# VR_joypad.net
KiCad netlist of a schematic drawn in Altium Designer
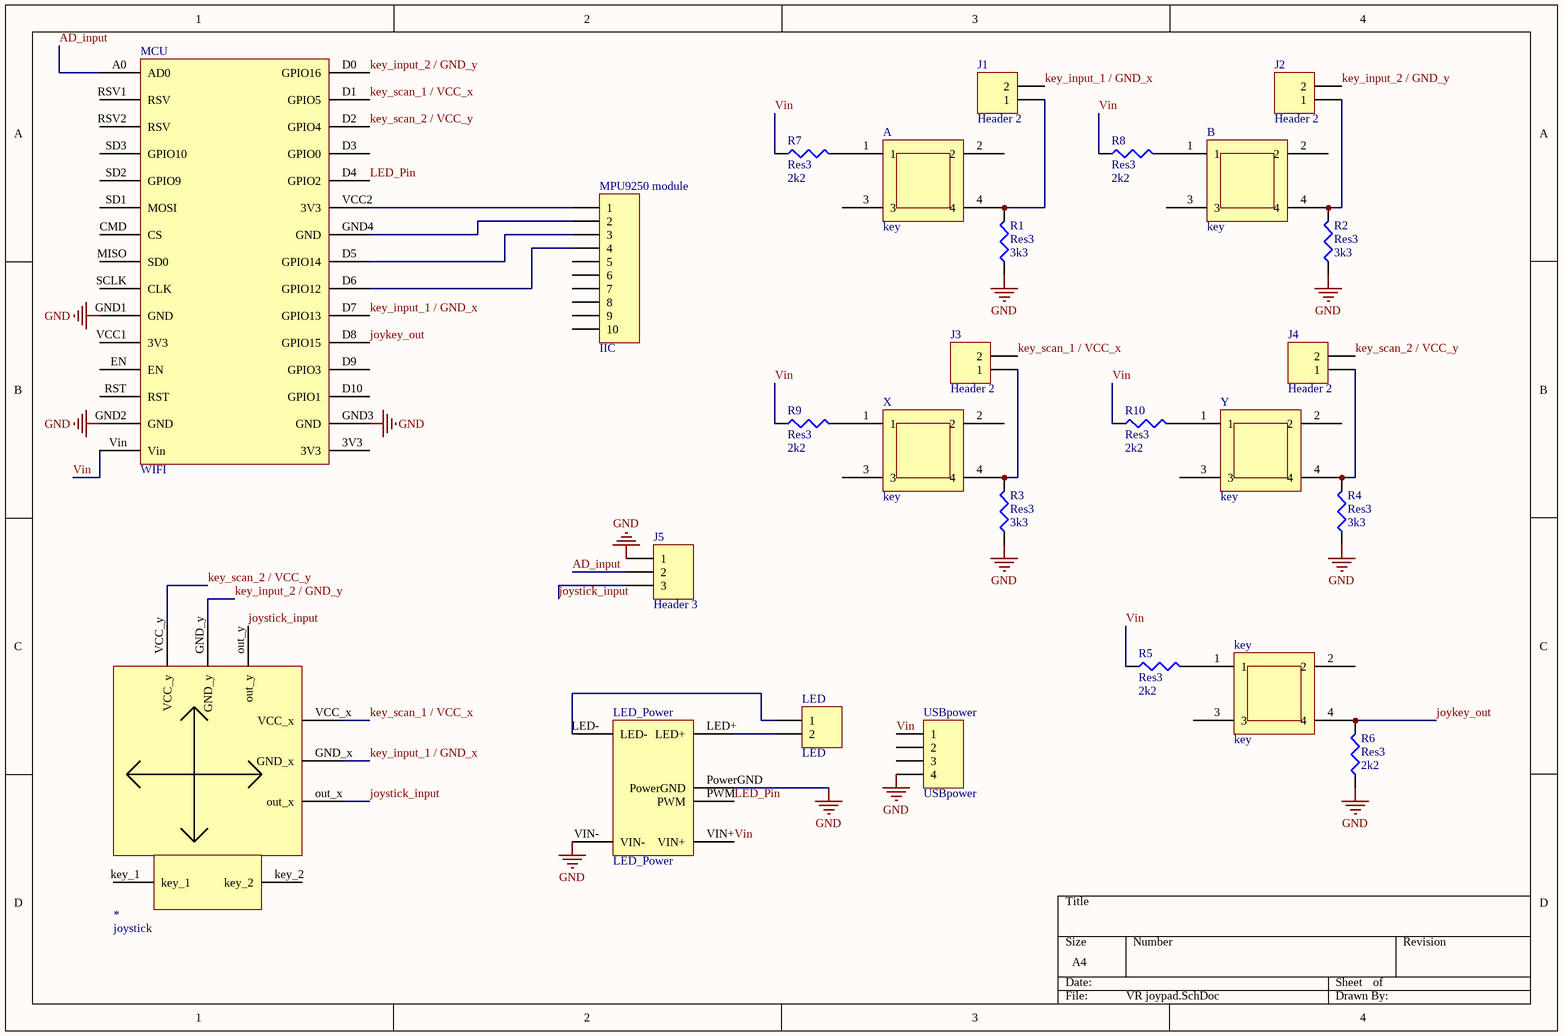
[diagram p0: VR joypad.SchDoc]

(export (version "E")
  (design (tool "Eeschema 10.0.6"))
  (components
    (comp (ref "*") (value "joystick") (footprint "joystick") (libsource (lib "VR joypad") (part "joystick")))
    (comp (ref "A")
      (value "key")
      (footprint "PCBComponent_1 - duplicate")
      (libsource (lib "VR joypad") (part "key"))
    )
    (comp (ref "B")
      (value "key")
      (footprint "PCBComponent_1 - duplicate")
      (libsource (lib "VR joypad") (part "key"))
    )
    (comp (ref "J1")
      (value "Header 2")
      (footprint "HDR1X2")
      (description "Header, 2-Pin")
      (fields (field (name "PUBLISHER") "Altium Limited"))
      (libsource (lib "") (part "Header 2_1"))
    )
    (comp (ref "J2")
      (value "Header 2")
      (footprint "HDR1X2")
      (description "Header, 2-Pin")
      (fields (field (name "PUBLISHER") "Altium Limited"))
      (libsource (lib "") (part "Header 2_1"))
    )
    (comp (ref "J3")
      (value "Header 2")
      (footprint "HDR1X2")
      (description "Header, 2-Pin")
      (fields (field (name "PUBLISHER") "Altium Limited"))
      (libsource (lib "") (part "Header 2_1"))
    )
    (comp (ref "J4")
      (value "Header 2")
      (footprint "HDR1X2")
      (description "Header, 2-Pin")
      (fields (field (name "PUBLISHER") "Altium Limited"))
      (libsource (lib "") (part "Header 2_1"))
    )
    (comp (ref "J5")
      (value "Header 3")
      (footprint "HDR1X3")
      (description "Header, 3-Pin")
      (fields (field (name "PUBLISHER") "Altium Limited"))
      (libsource (lib "Miscellaneous Connectors") (part "Header 3"))
    )
    (comp (ref "key")
      (value "key")
      (footprint "PCBComponent_1 - duplicate")
      (libsource (lib "VR joypad") (part "key"))
    )
    (comp (ref "LED")
      (value "LED")
      (footprint "HDR1X2")
      (description "Header, 2-Pin")
      (fields (field (name "PUBLISHER") "Altium Limited"))
      (libsource (lib "Miscellaneous Connectors") (part "Header 2"))
    )
    (comp (ref "LED_Power")
      (value "LED_Power")
      (footprint "PCBComponent_1 - duplicate1")
      (libsource (lib "VR joypad") (part "Power"))
    )
    (comp (ref "MCU")
      (value "WIFI")
      (footprint "PCBComponent_1")
      (libsource (lib "VR joypad") (part "Component_1"))
    )
    (comp (ref "MPU9250 module")
      (value "IIC")
      (footprint "HDR1X10")
      (description "Header, 10-Pin")
      (fields (field (name "PUBLISHER") "Altium Limited"))
      (libsource (lib "Miscellaneous Connectors") (part "Header 10"))
    )
    (comp (ref "R1")
      (value "Res3")
      (footprint "6-0805_N")
      (description "Resistor")
      (fields (field (name "ALTIUM_VALUE") "3k3") (field (name "PUBLISHER") "Altium Limited"))
      (libsource (lib "Miscellaneous Devices") (part "Res3"))
    )
    (comp (ref "R2")
      (value "Res3")
      (footprint "6-0805_N")
      (description "Resistor")
      (fields (field (name "ALTIUM_VALUE") "3k3") (field (name "PUBLISHER") "Altium Limited"))
      (libsource (lib "Miscellaneous Devices") (part "Res3"))
    )
    (comp (ref "R3")
      (value "Res3")
      (footprint "6-0805_N")
      (description "Resistor")
      (fields (field (name "ALTIUM_VALUE") "3k3") (field (name "PUBLISHER") "Altium Limited"))
      (libsource (lib "Miscellaneous Devices") (part "Res3"))
    )
    (comp (ref "R4")
      (value "Res3")
      (footprint "6-0805_N")
      (description "Resistor")
      (fields (field (name "ALTIUM_VALUE") "3k3") (field (name "PUBLISHER") "Altium Limited"))
      (libsource (lib "Miscellaneous Devices") (part "Res3"))
    )
    (comp (ref "R5")
      (value "Res3")
      (footprint "6-0805_N")
      (description "Resistor")
      (fields (field (name "ALTIUM_VALUE") "2k2") (field (name "PUBLISHER") "Altium Limited"))
      (libsource (lib "Miscellaneous Devices") (part "Res3"))
    )
    (comp (ref "R6")
      (value "Res3")
      (footprint "6-0805_N")
      (description "Resistor")
      (fields (field (name "ALTIUM_VALUE") "2k2") (field (name "PUBLISHER") "Altium Limited"))
      (libsource (lib "Miscellaneous Devices") (part "Res3"))
    )
    (comp (ref "R7")
      (value "Res3")
      (footprint "6-0805_N")
      (description "Resistor")
      (fields (field (name "ALTIUM_VALUE") "2k2") (field (name "PUBLISHER") "Altium Limited"))
      (libsource (lib "Miscellaneous Devices") (part "Res3"))
    )
    (comp (ref "R8")
      (value "Res3")
      (footprint "6-0805_N")
      (description "Resistor")
      (fields (field (name "ALTIUM_VALUE") "2k2") (field (name "PUBLISHER") "Altium Limited"))
      (libsource (lib "Miscellaneous Devices") (part "Res3"))
    )
    (comp (ref "R9")
      (value "Res3")
      (footprint "6-0805_N")
      (description "Resistor")
      (fields (field (name "ALTIUM_VALUE") "2k2") (field (name "PUBLISHER") "Altium Limited"))
      (libsource (lib "Miscellaneous Devices") (part "Res3"))
    )
    (comp (ref "R10")
      (value "Res3")
      (footprint "6-0805_N")
      (description "Resistor")
      (fields (field (name "ALTIUM_VALUE") "2k2") (field (name "PUBLISHER") "Altium Limited"))
      (libsource (lib "Miscellaneous Devices") (part "Res3"))
    )
    (comp (ref "USBpower")
      (value "USBpower")
      (footprint "HDR1X4")
      (description "Header, 4-Pin")
      (fields (field (name "PUBLISHER") "Altium Limited"))
      (libsource (lib "Miscellaneous Connectors") (part "Header 4"))
    )
    (comp (ref "X")
      (value "key")
      (footprint "PCBComponent_1 - duplicate")
      (libsource (lib "VR joypad") (part "key"))
    )
    (comp (ref "Y")
      (value "key")
      (footprint "PCBComponent_1 - duplicate")
      (libsource (lib "VR joypad") (part "key"))
    )
  )
  (nets
    (net (code "1") (name "/AD_input") (class "Default")
      (node (ref "J5") (pin "2") (pinfunction "2_2") (pintype "passive"))
      (node (ref "MCU") (pin "A0") (pinfunction "AD0_A0") (pintype "passive"))
    )
    (net (code "2") (name "/LED_Pin") (class "Default")
      (node (ref "LED_Power") (pin "PWM") (pinfunction "PWM_PWM") (pintype "passive"))
      (node (ref "MCU") (pin "D4") (pinfunction "GPIO2_D4") (pintype "passive"))
    )
    (net (code "3") (name "/Vin") (class "Default")
      (node (ref "LED_Power") (pin "VIN+") (pinfunction "VIN+_VIN+") (pintype "passive"))
      (node (ref "MCU") (pin "Vin") (pinfunction "Vin_Vin") (pintype "passive"))
      (node (ref "R10") (pin "1") (pinfunction "1_1") (pintype "passive"))
      (node (ref "R5") (pin "1") (pinfunction "1_1") (pintype "passive"))
      (node (ref "R7") (pin "1") (pinfunction "1_1") (pintype "passive"))
      (node (ref "R8") (pin "1") (pinfunction "1_1") (pintype "passive"))
      (node (ref "R9") (pin "1") (pinfunction "1_1") (pintype "passive"))
      (node (ref "USBpower") (pin "1") (pinfunction "1_1") (pintype "passive"))
    )
    (net (code "4") (name "/joykey_out") (class "Default")
      (node (ref "MCU") (pin "D8") (pinfunction "GPIO15_D8") (pintype "passive"))
      (node (ref "R6") (pin "2") (pinfunction "2_2") (pintype "passive"))
      (node (ref "key") (pin "4") (pinfunction "4_4") (pintype "passive"))
    )
    (net (code "5") (name "/joystick_input") (class "Default")
      (node (ref "*") (pin "out_x") (pinfunction "out_x_out_x") (pintype "passive"))
      (node (ref "*") (pin "out_y") (pinfunction "out_y_out_y") (pintype "passive"))
      (node (ref "J5") (pin "3") (pinfunction "3_3") (pintype "passive"))
    )
    (net (code "6") (name "/key_input_1 {slash} GND_x") (class "Default")
      (node (ref "*") (pin "GND_x") (pinfunction "GND_x_GND_x") (pintype "passive"))
      (node (ref "J1") (pin "2") (pinfunction "2_2") (pintype "passive"))
      (node (ref "MCU") (pin "D7") (pinfunction "GPIO13_D7") (pintype "passive"))
    )
    (net (code "7") (name "/key_input_2 {slash} GND_y") (class "Default")
      (node (ref "*") (pin "GND_y") (pinfunction "GND_y_GND_y") (pintype "passive"))
      (node (ref "J2") (pin "2") (pinfunction "2_2") (pintype "passive"))
      (node (ref "MCU") (pin "D0") (pinfunction "GPIO16_D0") (pintype "passive"))
    )
    (net (code "8") (name "/key_scan_1 {slash} VCC_x") (class "Default")
      (node (ref "*") (pin "VCC_x") (pinfunction "VCC_x_VCC_x") (pintype "passive"))
      (node (ref "J3") (pin "2") (pinfunction "2_2") (pintype "passive"))
      (node (ref "MCU") (pin "D1") (pinfunction "GPIO5_D1") (pintype "passive"))
    )
    (net (code "9") (name "/key_scan_2 {slash} VCC_y") (class "Default")
      (node (ref "*") (pin "VCC_y") (pinfunction "VCC_y_VCC_y") (pintype "passive"))
      (node (ref "J4") (pin "2") (pinfunction "2_2") (pintype "passive"))
      (node (ref "MCU") (pin "D2") (pinfunction "GPIO4_D2") (pintype "passive"))
    )
    (net (code "10") (name "GND") (class "Default")
      (node (ref "J5") (pin "1") (pinfunction "1_1") (pintype "passive"))
      (node (ref "LED_Power") (pin "PowerGND") (pinfunction "PowerGND_PowerGND") (pintype "passive"))
      (node (ref "LED_Power") (pin "VIN-") (pinfunction "VIN-_VIN-") (pintype "passive"))
      (node (ref "MCU") (pin "GND1") (pinfunction "GND_GND1") (pintype "passive"))
      (node (ref "MCU") (pin "GND2") (pinfunction "GND_GND2") (pintype "passive"))
      (node (ref "MCU") (pin "GND3") (pinfunction "GND_GND3") (pintype "passive"))
      (node (ref "R1") (pin "1") (pinfunction "1_1") (pintype "passive"))
      (node (ref "R2") (pin "1") (pinfunction "1_1") (pintype "passive"))
      (node (ref "R3") (pin "1") (pinfunction "1_1") (pintype "passive"))
      (node (ref "R4") (pin "1") (pinfunction "1_1") (pintype "passive"))
      (node (ref "R6") (pin "1") (pinfunction "1_1") (pintype "passive"))
      (node (ref "USBpower") (pin "4") (pinfunction "4_4") (pintype "passive"))
    )
    (net (code "11") (name "Net-(A-Pad1)") (class "Default")
      (node (ref "A") (pin "1") (pinfunction "1_1") (pintype "passive"))
      (node (ref "R7") (pin "2") (pinfunction "2_2") (pintype "passive"))
    )
    (net (code "12") (name "Net-(A-Pad4)") (class "Default")
      (node (ref "A") (pin "4") (pinfunction "4_4") (pintype "passive"))
      (node (ref "J1") (pin "1") (pinfunction "1_1") (pintype "passive"))
      (node (ref "R1") (pin "2") (pinfunction "2_2") (pintype "passive"))
    )
    (net (code "13") (name "Net-(B-Pad1)") (class "Default")
      (node (ref "B") (pin "1") (pinfunction "1_1") (pintype "passive"))
      (node (ref "R8") (pin "2") (pinfunction "2_2") (pintype "passive"))
    )
    (net (code "14") (name "Net-(B-Pad4)") (class "Default")
      (node (ref "B") (pin "4") (pinfunction "4_4") (pintype "passive"))
      (node (ref "J2") (pin "1") (pinfunction "1_1") (pintype "passive"))
      (node (ref "R2") (pin "2") (pinfunction "2_2") (pintype "passive"))
    )
    (net (code "15") (name "Net-(J3-Pad1)") (class "Default")
      (node (ref "J3") (pin "1") (pinfunction "1_1") (pintype "passive"))
      (node (ref "R3") (pin "2") (pinfunction "2_2") (pintype "passive"))
      (node (ref "X") (pin "4") (pinfunction "4_4") (pintype "passive"))
    )
    (net (code "16") (name "Net-(J4-Pad1)") (class "Default")
      (node (ref "J4") (pin "1") (pinfunction "1_1") (pintype "passive"))
      (node (ref "R4") (pin "2") (pinfunction "2_2") (pintype "passive"))
      (node (ref "Y") (pin "4") (pinfunction "4_4") (pintype "passive"))
    )
    (net (code "17") (name "Net-(LED-Pad1)") (class "Default")
      (node (ref "LED") (pin "1") (pinfunction "1_1") (pintype "passive"))
      (node (ref "LED_Power") (pin "LED-") (pinfunction "LED-_LED-") (pintype "passive"))
    )
    (net (code "18") (name "Net-(LED-Pad2)") (class "Default")
      (node (ref "LED") (pin "2") (pinfunction "2_2") (pintype "passive"))
      (node (ref "LED_Power") (pin "LED+") (pinfunction "LED+_LED+") (pintype "passive"))
    )
    (net (code "19") (name "Net-(MCU-3V3-PadVCC2)") (class "Default")
      (node (ref "MCU") (pin "VCC2") (pinfunction "3V3_VCC2") (pintype "passive"))
      (node (ref "MPU9250 module") (pin "1") (pinfunction "1_1") (pintype "passive"))
    )
    (net (code "20") (name "Net-(MCU-GND-PadGND4)") (class "Default")
      (node (ref "MCU") (pin "GND4") (pinfunction "GND_GND4") (pintype "passive"))
      (node (ref "MPU9250 module") (pin "2") (pinfunction "2_2") (pintype "passive"))
    )
    (net (code "21") (name "Net-(MCU-GPIO12)") (class "Default")
      (node (ref "MCU") (pin "D6") (pinfunction "GPIO12_D6") (pintype "passive"))
      (node (ref "MPU9250 module") (pin "4") (pinfunction "4_4") (pintype "passive"))
    )
    (net (code "22") (name "Net-(MCU-GPIO14)") (class "Default")
      (node (ref "MCU") (pin "D5") (pinfunction "GPIO14_D5") (pintype "passive"))
      (node (ref "MPU9250 module") (pin "3") (pinfunction "3_3") (pintype "passive"))
    )
    (net (code "23") (name "Net-(R5-Pad2)") (class "Default")
      (node (ref "R5") (pin "2") (pinfunction "2_2") (pintype "passive"))
      (node (ref "key") (pin "1") (pinfunction "1_1") (pintype "passive"))
    )
    (net (code "24") (name "Net-(R9-Pad2)") (class "Default")
      (node (ref "R9") (pin "2") (pinfunction "2_2") (pintype "passive"))
      (node (ref "X") (pin "1") (pinfunction "1_1") (pintype "passive"))
    )
    (net (code "25") (name "Net-(R10-Pad2)") (class "Default")
      (node (ref "R10") (pin "2") (pinfunction "2_2") (pintype "passive"))
      (node (ref "Y") (pin "1") (pinfunction "1_1") (pintype "passive"))
    )
    (net (code "26") (name "unconnected-(*-Padkey_1)") (class "Default")
      (node (ref "*") (pin "key_1") (pinfunction "key_1_key_1") (pintype "passive"))
    )
    (net (code "27") (name "unconnected-(*-Padkey_2)") (class "Default")
      (node (ref "*") (pin "key_2") (pinfunction "key_2_key_2") (pintype "passive"))
    )
    (net (code "28") (name "unconnected-(A-Pad2)") (class "Default")
      (node (ref "A") (pin "2") (pinfunction "2_2") (pintype "passive"))
    )
    (net (code "29") (name "unconnected-(A-Pad3)") (class "Default")
      (node (ref "A") (pin "3") (pinfunction "3_3") (pintype "passive"))
    )
    (net (code "30") (name "unconnected-(B-Pad2)") (class "Default")
      (node (ref "B") (pin "2") (pinfunction "2_2") (pintype "passive"))
    )
    (net (code "31") (name "unconnected-(B-Pad3)") (class "Default")
      (node (ref "B") (pin "3") (pinfunction "3_3") (pintype "passive"))
    )
    (net (code "32") (name "unconnected-(MCU-3V3-PadVCC1)") (class "Default")
      (node (ref "MCU") (pin "VCC1") (pinfunction "3V3_VCC1") (pintype "passive"))
    )
    (net (code "33") (name "unconnected-(MCU-CLK-PadSCLK)") (class "Default")
      (node (ref "MCU") (pin "SCLK") (pinfunction "CLK_SCLK") (pintype "passive"))
    )
    (net (code "34") (name "unconnected-(MCU-CS-PadCMD)") (class "Default")
      (node (ref "MCU") (pin "CMD") (pinfunction "CS_CMD") (pintype "passive"))
    )
    (net (code "35") (name "unconnected-(MCU-GPIO0-PadD3)") (class "Default")
      (node (ref "MCU") (pin "D3") (pinfunction "GPIO0_D3") (pintype "passive"))
    )
    (net (code "36") (name "unconnected-(MCU-GPIO1-PadD10)") (class "Default")
      (node (ref "MCU") (pin "D10") (pinfunction "GPIO1_D10") (pintype "passive"))
    )
    (net (code "37") (name "unconnected-(MCU-GPIO3-PadD9)") (class "Default")
      (node (ref "MCU") (pin "D9") (pinfunction "GPIO3_D9") (pintype "passive"))
    )
    (net (code "38") (name "unconnected-(MCU-GPIO9-PadSD2)") (class "Default")
      (node (ref "MCU") (pin "SD2") (pinfunction "GPIO9_SD2") (pintype "passive"))
    )
    (net (code "39") (name "unconnected-(MCU-GPIO10-PadSD3)") (class "Default")
      (node (ref "MCU") (pin "SD3") (pinfunction "GPIO10_SD3") (pintype "passive"))
    )
    (net (code "40") (name "unconnected-(MCU-MOSI-PadSD1)") (class "Default")
      (node (ref "MCU") (pin "SD1") (pinfunction "MOSI_SD1") (pintype "passive"))
    )
    (net (code "41") (name "unconnected-(MCU-Pad3V3)") (class "Default")
      (node (ref "MCU") (pin "3V3") (pinfunction "3V3_3V3") (pintype "passive"))
    )
    (net (code "42") (name "unconnected-(MCU-PadEN)") (class "Default")
      (node (ref "MCU") (pin "EN") (pinfunction "EN_EN") (pintype "passive"))
    )
    (net (code "43") (name "unconnected-(MCU-PadRST)") (class "Default")
      (node (ref "MCU") (pin "RST") (pinfunction "RST_RST") (pintype "passive"))
    )
    (net (code "44") (name "unconnected-(MCU-RSV-PadRSV1)") (class "Default")
      (node (ref "MCU") (pin "RSV1") (pinfunction "RSV_RSV1") (pintype "passive"))
    )
    (net (code "45") (name "unconnected-(MCU-RSV-PadRSV2)") (class "Default")
      (node (ref "MCU") (pin "RSV2") (pinfunction "RSV_RSV2") (pintype "passive"))
    )
    (net (code "46") (name "unconnected-(MCU-SD0-PadMISO)") (class "Default")
      (node (ref "MCU") (pin "MISO") (pinfunction "SD0_MISO") (pintype "passive"))
    )
    (net (code "47") (name "unconnected-(MPU9250 module-Pad5)") (class "Default")
      (node (ref "MPU9250 module") (pin "5") (pinfunction "5_5") (pintype "passive"))
    )
    (net (code "48") (name "unconnected-(MPU9250 module-Pad6)") (class "Default")
      (node (ref "MPU9250 module") (pin "6") (pinfunction "6_6") (pintype "passive"))
    )
    (net (code "49") (name "unconnected-(MPU9250 module-Pad7)") (class "Default")
      (node (ref "MPU9250 module") (pin "7") (pinfunction "7_7") (pintype "passive"))
    )
    (net (code "50") (name "unconnected-(MPU9250 module-Pad8)") (class "Default")
      (node (ref "MPU9250 module") (pin "8") (pinfunction "8_8") (pintype "passive"))
    )
    (net (code "51") (name "unconnected-(MPU9250 module-Pad9)") (class "Default")
      (node (ref "MPU9250 module") (pin "9") (pinfunction "9_9") (pintype "passive"))
    )
    (net (code "52") (name "unconnected-(MPU9250 module-Pad10)") (class "Default")
      (node (ref "MPU9250 module") (pin "10") (pinfunction "10_10") (pintype "passive"))
    )
    (net (code "53") (name "unconnected-(USBpower-Pad2)") (class "Default")
      (node (ref "USBpower") (pin "2") (pinfunction "2_2") (pintype "passive"))
    )
    (net (code "54") (name "unconnected-(USBpower-Pad3)") (class "Default")
      (node (ref "USBpower") (pin "3") (pinfunction "3_3") (pintype "passive"))
    )
    (net (code "55") (name "unconnected-(X-Pad2)") (class "Default")
      (node (ref "X") (pin "2") (pinfunction "2_2") (pintype "passive"))
    )
    (net (code "56") (name "unconnected-(X-Pad3)") (class "Default")
      (node (ref "X") (pin "3") (pinfunction "3_3") (pintype "passive"))
    )
    (net (code "57") (name "unconnected-(Y-Pad2)") (class "Default")
      (node (ref "Y") (pin "2") (pinfunction "2_2") (pintype "passive"))
    )
    (net (code "58") (name "unconnected-(Y-Pad3)") (class "Default")
      (node (ref "Y") (pin "3") (pinfunction "3_3") (pintype "passive"))
    )
    (net (code "59") (name "unconnected-(key-Pad2)") (class "Default")
      (node (ref "key") (pin "2") (pinfunction "2_2") (pintype "passive"))
    )
    (net (code "60") (name "unconnected-(key-Pad3)") (class "Default")
      (node (ref "key") (pin "3") (pinfunction "3_3") (pintype "passive"))
    )
  )
)
